# V__8.net
KiCad netlist of a schematic drawn in Altium Designer
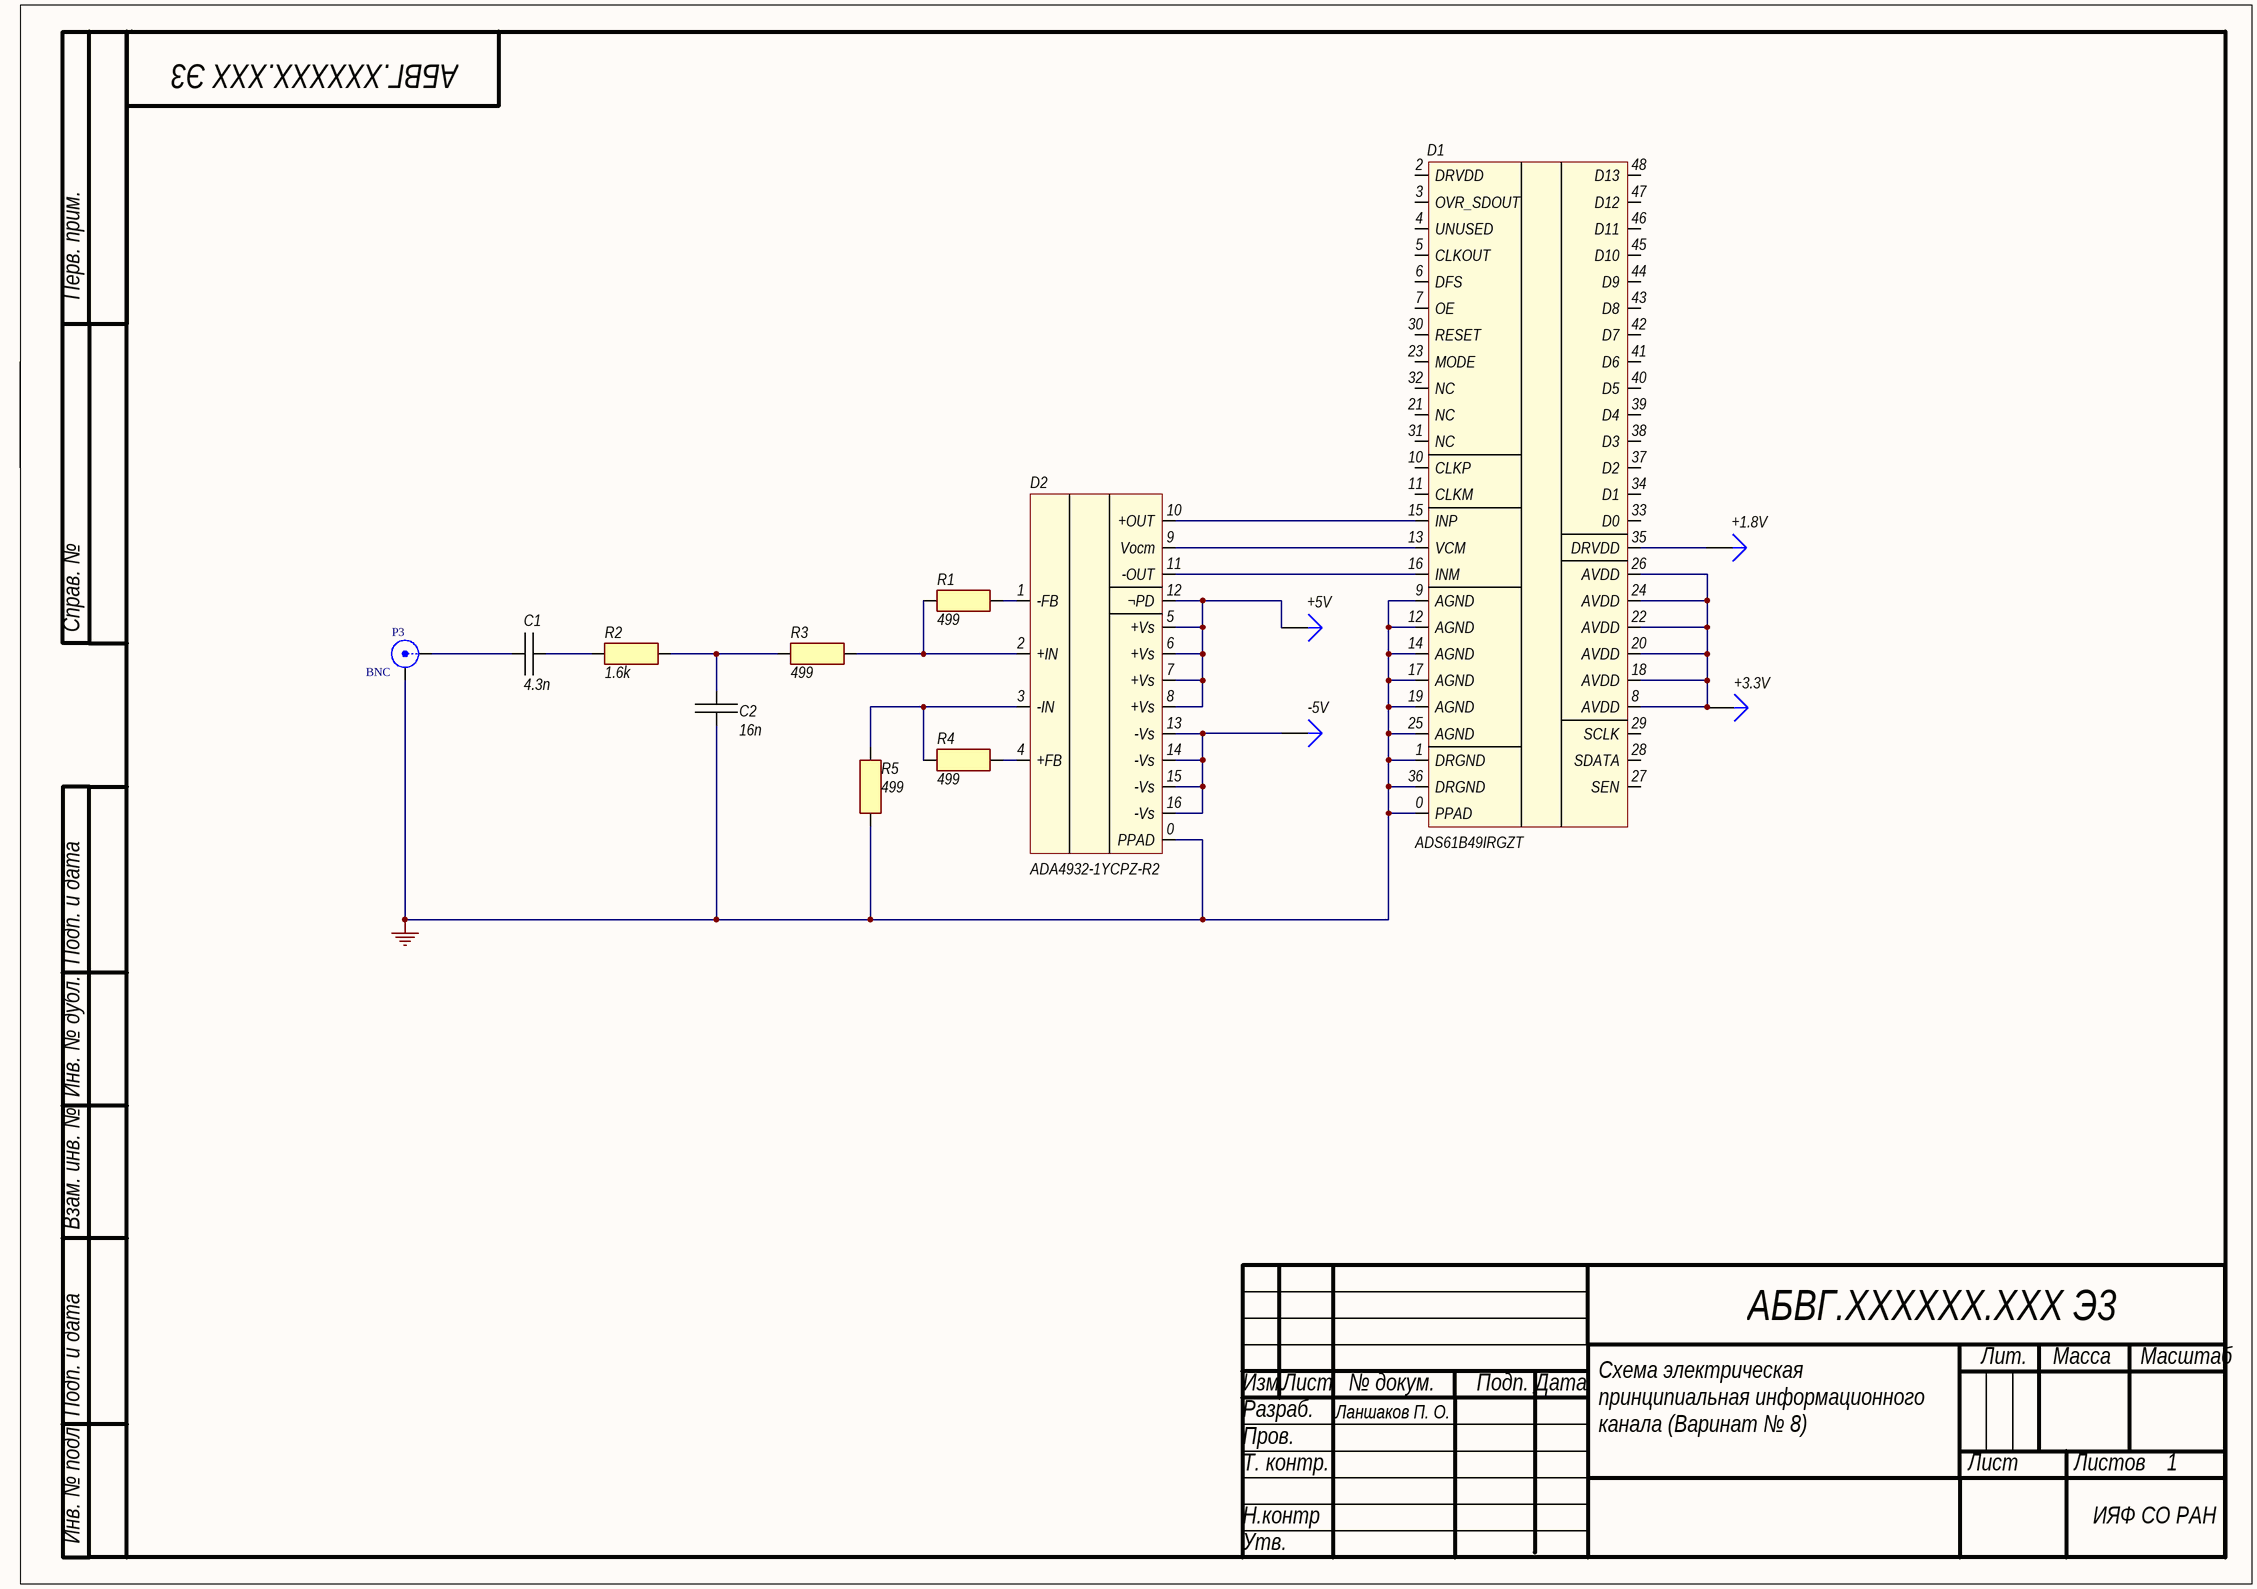
[diagram p0: V_№8.SchDoc]

(export (version "E")
  (design (tool "Eeschema 10.0.6"))
  (components
    (comp (ref "+1.8V")
      (value "Plug")
      (footprint "PIN1")
      (fields (field (name "PUBLISHER") "Altium Limited"))
      (libsource (lib "Miscellaneous Connectors") (part "Plug"))
    )
    (comp (ref "+3.3V")
      (value "Plug")
      (footprint "PIN1")
      (fields (field (name "PUBLISHER") "Altium Limited"))
      (libsource (lib "Miscellaneous Connectors") (part "Plug"))
    )
    (comp (ref "+5V")
      (value "Plug")
      (footprint "PIN1")
      (fields (field (name "PUBLISHER") "Altium Limited"))
      (libsource (lib "Miscellaneous Connectors") (part "Plug"))
    )
    (comp (ref "-5V")
      (value "Plug")
      (footprint "PIN1")
      (fields (field (name "PUBLISHER") "Altium Limited"))
      (libsource (lib "Miscellaneous Connectors") (part "Plug"))
    )
    (comp (ref "C1") (value "4.3п") (footprint "0101") (libsource (lib "V_№8") (part "Capacitor")))
    (comp (ref "C2") (value "16п") (footprint "0101") (libsource (lib "V_№8") (part "Capacitor")))
    (comp (ref "D1")
      (value "ADS61B49IRGZT")
      (footprint "QFN50P700X700X100_HS-49N")
      (fields (field (name "MANUFACTURER") "Texas Instruments"))
      (libsource (lib "V_№8") (part "ADS61B49"))
    )
    (comp (ref "D2")
      (value "ADA4932-1YCPZ-R2")
      (footprint "QFN50P300X300X100_HS-17N")
      (fields (field (name "MANUFACTURER") "Analog Devices Inc."))
      (libsource (lib "V_№8") (part "ADA4932"))
    )
    (comp (ref "P3")
      (value "BNC")
      (footprint "BNC_RA CON")
      (description "BNC Elbow Connector")
      (fields (field (name "PUBLISHER") "Altium Limited"))
      (libsource (lib "Miscellaneous Connectors") (part "BNC"))
    )
    (comp (ref "R1") (value "499") (footprint "0201") (libsource (lib "V_№8") (part "Resistor")))
    (comp (ref "R2") (value "1.6k") (footprint "0201") (libsource (lib "V_№8") (part "Resistor")))
    (comp (ref "R3") (value "499") (footprint "0201") (libsource (lib "V_№8") (part "Resistor")))
    (comp (ref "R4") (value "499") (footprint "0201") (libsource (lib "V_№8") (part "Resistor")))
    (comp (ref "R5") (value "499") (footprint "0201") (libsource (lib "") (part "Resistor_1")))
  )
  (nets
    (net (code "1") (name "GND") (class "Default")
      (node (ref "C2") (pin "1") (pinfunction "-FB_1") (pintype "passive"))
      (node (ref "D1") (pin "0") (pinfunction "PPAD_0") (pintype "passive"))
      (node (ref "D1") (pin "1") (pinfunction "DRGND_1") (pintype "passive"))
      (node (ref "D1") (pin "12") (pinfunction "AGND_12") (pintype "passive"))
      (node (ref "D1") (pin "14") (pinfunction "AGND_14") (pintype "passive"))
      (node (ref "D1") (pin "17") (pinfunction "AGND_17") (pintype "passive"))
      (node (ref "D1") (pin "19") (pinfunction "AGND_19") (pintype "passive"))
      (node (ref "D1") (pin "25") (pinfunction "AGND_25") (pintype "passive"))
      (node (ref "D1") (pin "36") (pinfunction "DRGND_36") (pintype "passive"))
      (node (ref "D1") (pin "9") (pinfunction "AGND_9") (pintype "passive"))
      (node (ref "D2") (pin "0") (pinfunction "PPAD_0") (pintype "passive"))
      (node (ref "P3") (pin "2") (pinfunction "Y_2") (pintype "passive"))
      (node (ref "R5") (pin "2") (pinfunction "2_2") (pintype "passive"))
    )
    (net (code "2") (name "Net-(+1.8V-Pad1)") (class "Default")
      (node (ref "+1.8V") (pin "1") (pinfunction "1_1") (pintype "passive"))
      (node (ref "D1") (pin "35") (pinfunction "DRVDD_35") (pintype "passive"))
    )
    (net (code "3") (name "Net-(+3.3V-Pad1)") (class "Default")
      (node (ref "+3.3V") (pin "1") (pinfunction "1_1") (pintype "passive"))
      (node (ref "D1") (pin "18") (pinfunction "AVDD_18") (pintype "passive"))
      (node (ref "D1") (pin "20") (pinfunction "AVDD_20") (pintype "passive"))
      (node (ref "D1") (pin "22") (pinfunction "AVDD_22") (pintype "passive"))
      (node (ref "D1") (pin "24") (pinfunction "AVDD_24") (pintype "passive"))
      (node (ref "D1") (pin "26") (pinfunction "AVDD_26") (pintype "passive"))
      (node (ref "D1") (pin "8") (pinfunction "AVDD_8") (pintype "passive"))
    )
    (net (code "4") (name "Net-(-5V-Pad1)") (class "Default")
      (node (ref "-5V") (pin "1") (pinfunction "1_1") (pintype "passive"))
      (node (ref "D2") (pin "13") (pinfunction "-Vs_13") (pintype "passive"))
      (node (ref "D2") (pin "14") (pinfunction "-Vs_14") (pintype "passive"))
      (node (ref "D2") (pin "15") (pinfunction "-Vs_15") (pintype "passive"))
      (node (ref "D2") (pin "16") (pinfunction "-Vs_16") (pintype "passive"))
    )
    (net (code "5") (name "Net-(C1-+IN)") (class "Default")
      (node (ref "C1") (pin "2") (pinfunction "+IN_2") (pintype "passive"))
      (node (ref "R2") (pin "2") (pinfunction "2_2") (pintype "passive"))
    )
    (net (code "6") (name "Net-(C1--FB)") (class "Default")
      (node (ref "C1") (pin "1") (pinfunction "-FB_1") (pintype "passive"))
      (node (ref "P3") (pin "1") (pinfunction "X_1") (pintype "passive"))
    )
    (net (code "7") (name "Net-(C2-+IN)") (class "Default")
      (node (ref "C2") (pin "2") (pinfunction "+IN_2") (pintype "passive"))
      (node (ref "R2") (pin "1") (pinfunction "0_1") (pintype "passive"))
      (node (ref "R3") (pin "2") (pinfunction "2_2") (pintype "passive"))
    )
    (net (code "8") (name "Net-(D1-INM)") (class "Default")
      (node (ref "D1") (pin "16") (pinfunction "INM_16") (pintype "passive"))
      (node (ref "D2") (pin "11") (pinfunction "-OUT_11") (pintype "passive"))
    )
    (net (code "9") (name "Net-(D1-INP)") (class "Default")
      (node (ref "D1") (pin "15") (pinfunction "INP_15") (pintype "passive"))
      (node (ref "D2") (pin "10") (pinfunction "+OUT_10") (pintype "passive"))
    )
    (net (code "10") (name "Net-(D1-VCM)") (class "Default")
      (node (ref "D1") (pin "13") (pinfunction "VCM_13") (pintype "passive"))
      (node (ref "D2") (pin "9") (pinfunction "Vocm_9") (pintype "passive"))
    )
    (net (code "11") (name "Net-(D2-+FB)") (class "Default")
      (node (ref "D2") (pin "4") (pinfunction "+FB_4") (pintype "passive"))
      (node (ref "R4") (pin "1") (pinfunction "0_1") (pintype "passive"))
    )
    (net (code "12") (name "Net-(D2-+IN)") (class "Default")
      (node (ref "D2") (pin "2") (pinfunction "+IN_2") (pintype "passive"))
      (node (ref "R1") (pin "2") (pinfunction "2_2") (pintype "passive"))
      (node (ref "R3") (pin "1") (pinfunction "0_1") (pintype "passive"))
    )
    (net (code "13") (name "Net-(D2--FB)") (class "Default")
      (node (ref "D2") (pin "1") (pinfunction "-FB_1") (pintype "passive"))
      (node (ref "R1") (pin "1") (pinfunction "0_1") (pintype "passive"))
    )
    (net (code "14") (name "Net-(D2--IN)") (class "Default")
      (node (ref "D2") (pin "3") (pinfunction "-IN_3") (pintype "passive"))
      (node (ref "R4") (pin "2") (pinfunction "2_2") (pintype "passive"))
      (node (ref "R5") (pin "1") (pinfunction "0_1") (pintype "passive"))
    )
    (net (code "15") (name "Net-(D2-¬PD)") (class "Default")
      (node (ref "+5V") (pin "1") (pinfunction "1_1") (pintype "passive"))
      (node (ref "D2") (pin "12") (pinfunction "¬PD_12") (pintype "passive"))
      (node (ref "D2") (pin "5") (pinfunction "+Vs_5") (pintype "passive"))
      (node (ref "D2") (pin "6") (pinfunction "+Vs_6") (pintype "passive"))
      (node (ref "D2") (pin "7") (pinfunction "+Vs_7") (pintype "passive"))
      (node (ref "D2") (pin "8") (pinfunction "+Vs_8") (pintype "passive"))
    )
    (net (code "16") (name "unconnected-(D1-CLKM-Pad11)") (class "Default")
      (node (ref "D1") (pin "11") (pinfunction "CLKM_11") (pintype "passive"))
    )
    (net (code "17") (name "unconnected-(D1-CLKOUT-Pad5)") (class "Default")
      (node (ref "D1") (pin "5") (pinfunction "CLKOUT_5") (pintype "passive"))
    )
    (net (code "18") (name "unconnected-(D1-CLKP-Pad10)") (class "Default")
      (node (ref "D1") (pin "10") (pinfunction "CLKP_10") (pintype "passive"))
    )
    (net (code "19") (name "unconnected-(D1-D0-Pad33)") (class "Default")
      (node (ref "D1") (pin "33") (pinfunction "D0_33") (pintype "passive"))
    )
    (net (code "20") (name "unconnected-(D1-D1-Pad34)") (class "Default")
      (node (ref "D1") (pin "34") (pinfunction "D1_34") (pintype "passive"))
    )
    (net (code "21") (name "unconnected-(D1-D2-Pad37)") (class "Default")
      (node (ref "D1") (pin "37") (pinfunction "D2_37") (pintype "passive"))
    )
    (net (code "22") (name "unconnected-(D1-D3-Pad38)") (class "Default")
      (node (ref "D1") (pin "38") (pinfunction "D3_38") (pintype "passive"))
    )
    (net (code "23") (name "unconnected-(D1-D4-Pad39)") (class "Default")
      (node (ref "D1") (pin "39") (pinfunction "D4_39") (pintype "passive"))
    )
    (net (code "24") (name "unconnected-(D1-D5-Pad40)") (class "Default")
      (node (ref "D1") (pin "40") (pinfunction "D5_40") (pintype "passive"))
    )
    (net (code "25") (name "unconnected-(D1-D6-Pad41)") (class "Default")
      (node (ref "D1") (pin "41") (pinfunction "D6_41") (pintype "passive"))
    )
    (net (code "26") (name "unconnected-(D1-D7-Pad42)") (class "Default")
      (node (ref "D1") (pin "42") (pinfunction "D7_42") (pintype "passive"))
    )
    (net (code "27") (name "unconnected-(D1-D8-Pad43)") (class "Default")
      (node (ref "D1") (pin "43") (pinfunction "D8_43") (pintype "passive"))
    )
    (net (code "28") (name "unconnected-(D1-D9-Pad44)") (class "Default")
      (node (ref "D1") (pin "44") (pinfunction "D9_44") (pintype "passive"))
    )
    (net (code "29") (name "unconnected-(D1-D10-Pad45)") (class "Default")
      (node (ref "D1") (pin "45") (pinfunction "D10_45") (pintype "passive"))
    )
    (net (code "30") (name "unconnected-(D1-D11-Pad46)") (class "Default")
      (node (ref "D1") (pin "46") (pinfunction "D11_46") (pintype "passive"))
    )
    (net (code "31") (name "unconnected-(D1-D12-Pad47)") (class "Default")
      (node (ref "D1") (pin "47") (pinfunction "D12_47") (pintype "passive"))
    )
    (net (code "32") (name "unconnected-(D1-D13-Pad48)") (class "Default")
      (node (ref "D1") (pin "48") (pinfunction "D13_48") (pintype "passive"))
    )
    (net (code "33") (name "unconnected-(D1-DFS-Pad6)") (class "Default")
      (node (ref "D1") (pin "6") (pinfunction "DFS_6") (pintype "passive"))
    )
    (net (code "34") (name "unconnected-(D1-DRVDD-Pad2)") (class "Default")
      (node (ref "D1") (pin "2") (pinfunction "DRVDD_2") (pintype "passive"))
    )
    (net (code "35") (name "unconnected-(D1-MODE-Pad23)") (class "Default")
      (node (ref "D1") (pin "23") (pinfunction "MODE_23") (pintype "passive"))
    )
    (net (code "36") (name "unconnected-(D1-NC-Pad21)") (class "Default")
      (node (ref "D1") (pin "21") (pinfunction "NC_21") (pintype "passive"))
    )
    (net (code "37") (name "unconnected-(D1-NC-Pad31)") (class "Default")
      (node (ref "D1") (pin "31") (pinfunction "NC_31") (pintype "passive"))
    )
    (net (code "38") (name "unconnected-(D1-NC-Pad32)") (class "Default")
      (node (ref "D1") (pin "32") (pinfunction "NC_32") (pintype "passive"))
    )
    (net (code "39") (name "unconnected-(D1-OE-Pad7)") (class "Default")
      (node (ref "D1") (pin "7") (pinfunction "OE_7") (pintype "passive"))
    )
    (net (code "40") (name "unconnected-(D1-OVR_SDOUT-Pad3)") (class "Default")
      (node (ref "D1") (pin "3") (pinfunction "OVR_SDOUT_3") (pintype "passive"))
    )
    (net (code "41") (name "unconnected-(D1-RESET-Pad30)") (class "Default")
      (node (ref "D1") (pin "30") (pinfunction "RESET_30") (pintype "passive"))
    )
    (net (code "42") (name "unconnected-(D1-SCLK-Pad29)") (class "Default")
      (node (ref "D1") (pin "29") (pinfunction "SCLK_29") (pintype "passive"))
    )
    (net (code "43") (name "unconnected-(D1-SDATA-Pad28)") (class "Default")
      (node (ref "D1") (pin "28") (pinfunction "SDATA_28") (pintype "passive"))
    )
    (net (code "44") (name "unconnected-(D1-SEN-Pad27)") (class "Default")
      (node (ref "D1") (pin "27") (pinfunction "SEN_27") (pintype "passive"))
    )
    (net (code "45") (name "unconnected-(D1-UNUSED-Pad4)") (class "Default")
      (node (ref "D1") (pin "4") (pinfunction "UNUSED_4") (pintype "passive"))
    )
  )
)
